# ppc_net.net
KiCad netlist of a schematic drawn in Altium Designer
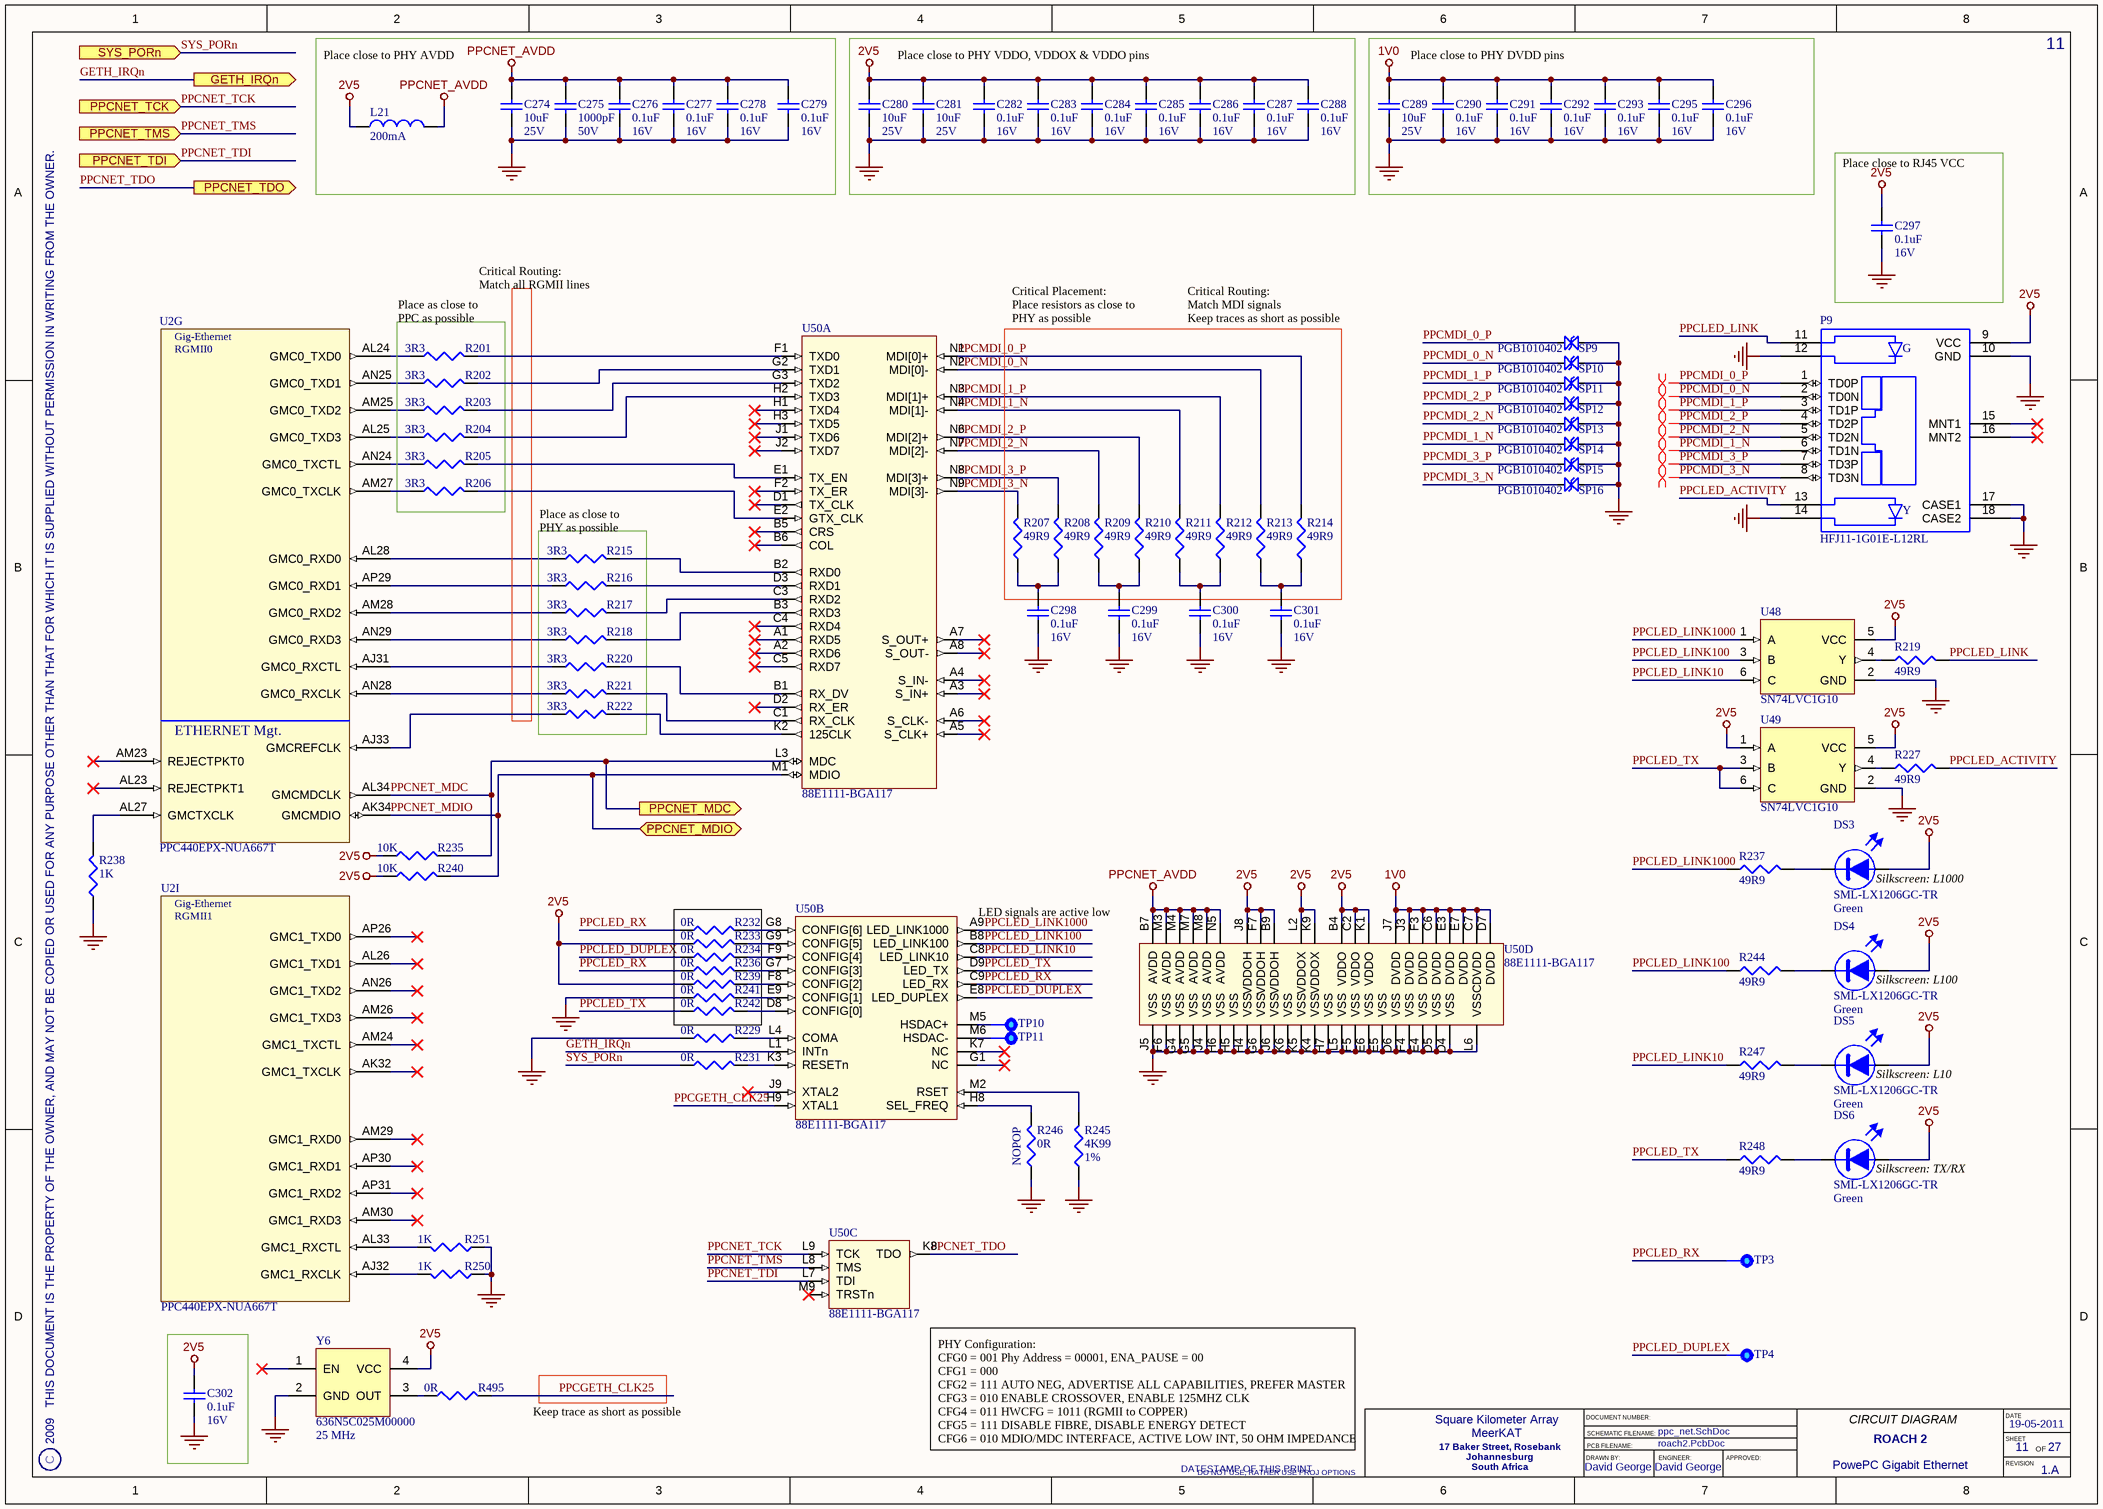
[diagram p0: ppc_net.SchDoc]

(export (version "E")
  (design (tool "Eeschema 10.0.6"))
  (components
    (comp (ref "C274")
      (value "10uF")
      (footprint "CAPC3225X200L")
      (description "10uF, Ceramic Capacitor")
      (fields
        (field (name "RATING") "25V")
        (field (name "MANUFACTURER") "MURATA")
        (field (name "PARTNUM") "GRM32DR61E106KA12L")
      )
      (libsource (lib "altium_db") (part "CapStd"))
    )
    (comp (ref "C275")
      (value "1000pF")
      (footprint "CAPC1005X55L")
      (description "1000pF, Ceramic Capacitor")
      (fields
        (field (name "RATING") "50V")
        (field (name "MANUFACTURER") "MURATA")
        (field (name "PARTNUM") "GRM155R61H102KA01D")
      )
      (libsource (lib "altium_db") (part "CapStd"))
    )
    (comp (ref "C276")
      (value "0.1uF")
      (footprint "CAPC1005X60L")
      (description "0.1uF, Ceramic Capacitor")
      (fields
        (field (name "RATING") "16V")
        (field (name "MANUFACTURER") "VENKEL")
        (field (name "PARTNUM") "C0402X7R160-104KN")
      )
      (libsource (lib "altium_db") (part "CapStd"))
    )
    (comp (ref "C277")
      (value "0.1uF")
      (footprint "CAPC1005X60L")
      (description "0.1uF, Ceramic Capacitor")
      (fields
        (field (name "RATING") "16V")
        (field (name "MANUFACTURER") "VENKEL")
        (field (name "PARTNUM") "C0402X7R160-104KN")
      )
      (libsource (lib "altium_db") (part "CapStd"))
    )
    (comp (ref "C278")
      (value "0.1uF")
      (footprint "CAPC1005X60L")
      (description "0.1uF, Ceramic Capacitor")
      (fields
        (field (name "RATING") "16V")
        (field (name "MANUFACTURER") "VENKEL")
        (field (name "PARTNUM") "C0402X7R160-104KN")
      )
      (libsource (lib "altium_db") (part "CapStd"))
    )
    (comp (ref "C279")
      (value "0.1uF")
      (footprint "CAPC1005X60L")
      (description "0.1uF, Ceramic Capacitor")
      (fields
        (field (name "RATING") "16V")
        (field (name "MANUFACTURER") "VENKEL")
        (field (name "PARTNUM") "C0402X7R160-104KN")
      )
      (libsource (lib "altium_db") (part "CapStd"))
    )
    (comp (ref "C280")
      (value "10uF")
      (footprint "CAPC3225X200L")
      (description "10uF, Ceramic Capacitor")
      (fields
        (field (name "RATING") "25V")
        (field (name "MANUFACTURER") "MURATA")
        (field (name "PARTNUM") "GRM32DR61E106KA12L")
      )
      (libsource (lib "altium_db") (part "CapStd"))
    )
    (comp (ref "C281")
      (value "10uF")
      (footprint "CAPC3225X200L")
      (description "10uF, Ceramic Capacitor")
      (fields
        (field (name "RATING") "25V")
        (field (name "MANUFACTURER") "MURATA")
        (field (name "PARTNUM") "GRM32DR61E106KA12L")
      )
      (libsource (lib "altium_db") (part "CapStd"))
    )
    (comp (ref "C282")
      (value "0.1uF")
      (footprint "CAPC1005X60L")
      (description "0.1uF, Ceramic Capacitor")
      (fields
        (field (name "RATING") "16V")
        (field (name "MANUFACTURER") "VENKEL")
        (field (name "PARTNUM") "C0402X7R160-104KN")
      )
      (libsource (lib "altium_db") (part "CapStd"))
    )
    (comp (ref "C283")
      (value "0.1uF")
      (footprint "CAPC1005X60L")
      (description "0.1uF, Ceramic Capacitor")
      (fields
        (field (name "RATING") "16V")
        (field (name "MANUFACTURER") "VENKEL")
        (field (name "PARTNUM") "C0402X7R160-104KN")
      )
      (libsource (lib "altium_db") (part "CapStd"))
    )
    (comp (ref "C284")
      (value "0.1uF")
      (footprint "CAPC1005X60L")
      (description "0.1uF, Ceramic Capacitor")
      (fields
        (field (name "RATING") "16V")
        (field (name "MANUFACTURER") "VENKEL")
        (field (name "PARTNUM") "C0402X7R160-104KN")
      )
      (libsource (lib "altium_db") (part "CapStd"))
    )
    (comp (ref "C285")
      (value "0.1uF")
      (footprint "CAPC1005X60L")
      (description "0.1uF, Ceramic Capacitor")
      (fields
        (field (name "RATING") "16V")
        (field (name "MANUFACTURER") "VENKEL")
        (field (name "PARTNUM") "C0402X7R160-104KN")
      )
      (libsource (lib "altium_db") (part "CapStd"))
    )
    (comp (ref "C286")
      (value "0.1uF")
      (footprint "CAPC1005X60L")
      (description "0.1uF, Ceramic Capacitor")
      (fields
        (field (name "RATING") "16V")
        (field (name "MANUFACTURER") "VENKEL")
        (field (name "PARTNUM") "C0402X7R160-104KN")
      )
      (libsource (lib "altium_db") (part "CapStd"))
    )
    (comp (ref "C287")
      (value "0.1uF")
      (footprint "CAPC1005X60L")
      (description "0.1uF, Ceramic Capacitor")
      (fields
        (field (name "RATING") "16V")
        (field (name "MANUFACTURER") "VENKEL")
        (field (name "PARTNUM") "C0402X7R160-104KN")
      )
      (libsource (lib "altium_db") (part "CapStd"))
    )
    (comp (ref "C288")
      (value "0.1uF")
      (footprint "CAPC1005X60L")
      (description "0.1uF, Ceramic Capacitor")
      (fields
        (field (name "RATING") "16V")
        (field (name "MANUFACTURER") "VENKEL")
        (field (name "PARTNUM") "C0402X7R160-104KN")
      )
      (libsource (lib "altium_db") (part "CapStd"))
    )
    (comp (ref "C289")
      (value "10uF")
      (footprint "CAPC3225X200L")
      (description "10uF, Ceramic Capacitor")
      (fields
        (field (name "RATING") "25V")
        (field (name "MANUFACTURER") "MURATA")
        (field (name "PARTNUM") "GRM32DR61E106KA12L")
      )
      (libsource (lib "altium_db") (part "CapStd"))
    )
    (comp (ref "C290")
      (value "0.1uF")
      (footprint "CAPC1005X60L")
      (description "0.1uF, Ceramic Capacitor")
      (fields
        (field (name "RATING") "16V")
        (field (name "MANUFACTURER") "VENKEL")
        (field (name "PARTNUM") "C0402X7R160-104KN")
      )
      (libsource (lib "altium_db") (part "CapStd"))
    )
    (comp (ref "C291")
      (value "0.1uF")
      (footprint "CAPC1005X60L")
      (description "0.1uF, Ceramic Capacitor")
      (fields
        (field (name "RATING") "16V")
        (field (name "MANUFACTURER") "VENKEL")
        (field (name "PARTNUM") "C0402X7R160-104KN")
      )
      (libsource (lib "altium_db") (part "CapStd"))
    )
    (comp (ref "C292")
      (value "0.1uF")
      (footprint "CAPC1005X60L")
      (description "0.1uF, Ceramic Capacitor")
      (fields
        (field (name "RATING") "16V")
        (field (name "MANUFACTURER") "VENKEL")
        (field (name "PARTNUM") "C0402X7R160-104KN")
      )
      (libsource (lib "altium_db") (part "CapStd"))
    )
    (comp (ref "C293")
      (value "0.1uF")
      (footprint "CAPC1005X60L")
      (description "0.1uF, Ceramic Capacitor")
      (fields
        (field (name "RATING") "16V")
        (field (name "MANUFACTURER") "VENKEL")
        (field (name "PARTNUM") "C0402X7R160-104KN")
      )
      (libsource (lib "altium_db") (part "CapStd"))
    )
    (comp (ref "C295")
      (value "0.1uF")
      (footprint "CAPC1005X60L")
      (description "0.1uF, Ceramic Capacitor")
      (fields
        (field (name "RATING") "16V")
        (field (name "MANUFACTURER") "VENKEL")
        (field (name "PARTNUM") "C0402X7R160-104KN")
      )
      (libsource (lib "altium_db") (part "CapStd"))
    )
    (comp (ref "C296")
      (value "0.1uF")
      (footprint "CAPC1005X60L")
      (description "0.1uF, Ceramic Capacitor")
      (fields
        (field (name "RATING") "16V")
        (field (name "MANUFACTURER") "VENKEL")
        (field (name "PARTNUM") "C0402X7R160-104KN")
      )
      (libsource (lib "altium_db") (part "CapStd"))
    )
    (comp (ref "C297")
      (value "0.1uF")
      (footprint "CAPC1005X60L")
      (description "0.1uF, Ceramic Capacitor")
      (fields
        (field (name "RATING") "16V")
        (field (name "MANUFACTURER") "VENKEL")
        (field (name "PARTNUM") "C0402X7R160-104KN")
      )
      (libsource (lib "altium_db") (part "CapStd"))
    )
    (comp (ref "C298")
      (value "0.1uF")
      (footprint "CAPC1005X60L")
      (description "0.1uF, Ceramic Capacitor")
      (fields
        (field (name "RATING") "16V")
        (field (name "MANUFACTURER") "VENKEL")
        (field (name "PARTNUM") "C0402X7R160-104KN")
      )
      (libsource (lib "altium_db") (part "CapStd"))
    )
    (comp (ref "C299")
      (value "0.1uF")
      (footprint "CAPC1005X60L")
      (description "0.1uF, Ceramic Capacitor")
      (fields
        (field (name "RATING") "16V")
        (field (name "MANUFACTURER") "VENKEL")
        (field (name "PARTNUM") "C0402X7R160-104KN")
      )
      (libsource (lib "altium_db") (part "CapStd"))
    )
    (comp (ref "C300")
      (value "0.1uF")
      (footprint "CAPC1005X60L")
      (description "0.1uF, Ceramic Capacitor")
      (fields
        (field (name "RATING") "16V")
        (field (name "MANUFACTURER") "VENKEL")
        (field (name "PARTNUM") "C0402X7R160-104KN")
      )
      (libsource (lib "altium_db") (part "CapStd"))
    )
    (comp (ref "C301")
      (value "0.1uF")
      (footprint "CAPC1005X60L")
      (description "0.1uF, Ceramic Capacitor")
      (fields
        (field (name "RATING") "16V")
        (field (name "MANUFACTURER") "VENKEL")
        (field (name "PARTNUM") "C0402X7R160-104KN")
      )
      (libsource (lib "altium_db") (part "CapStd"))
    )
    (comp (ref "C302")
      (value "0.1uF")
      (footprint "CAPC1005X60L")
      (description "0.1uF, Ceramic Capacitor")
      (fields
        (field (name "RATING") "16V")
        (field (name "MANUFACTURER") "VENKEL")
        (field (name "PARTNUM") "C0402X7R160-104KN")
      )
      (libsource (lib "altium_db") (part "CapStd"))
    )
    (comp (ref "DS3")
      (value "SML-LX1206GC-TR")
      (footprint "LEDC3216X120N")
      (description "Green, Surface mount, LED, 1206")
      (fields (field (name "MANUFACTURER") "LUMEX") (field (name "COLOUR") "Green"))
      (libsource (lib "altium_db") (part "LEDSTD"))
    )
    (comp (ref "DS4")
      (value "SML-LX1206GC-TR")
      (footprint "LEDC3216X120N")
      (description "Green, Surface mount, LED, 1206")
      (fields (field (name "MANUFACTURER") "LUMEX") (field (name "COLOUR") "Green"))
      (libsource (lib "altium_db") (part "LEDSTD"))
    )
    (comp (ref "DS5")
      (value "SML-LX1206GC-TR")
      (footprint "LEDC3216X120N")
      (description "Green, Surface mount, LED, 1206")
      (fields (field (name "MANUFACTURER") "LUMEX") (field (name "COLOUR") "Green"))
      (libsource (lib "altium_db") (part "LEDSTD"))
    )
    (comp (ref "DS6")
      (value "SML-LX1206GC-TR")
      (footprint "LEDC3216X120N")
      (description "Green, Surface mount, LED, 1206")
      (fields (field (name "MANUFACTURER") "LUMEX") (field (name "COLOUR") "Green"))
      (libsource (lib "altium_db") (part "LEDSTD"))
    )
    (comp (ref "L21")
      (value "600R")
      (footprint "INDC2012X130L")
      (description "600 Ohm, Chip Ferrite Bead")
      (fields
        (field (name "RATING") "200mA")
        (field (name "MANUFACTURER") "Murata")
        (field (name "PARTNUM") "BLM21BD601SN1")
      )
      (libsource (lib "altium_db") (part "IndStd"))
    )
    (comp (ref "P9")
      (value "HFJ11-1G01E-L12RL")
      (footprint "HALO_HFJ11-1G02E-L55")
      (description "RJ45 with Integrated magnetic and dual LEDs")
      (fields (field (name "PARTNUM") "HFJ11-1G01E-L12RL") (field (name "MANUFACTURER") "HALO"))
      (libsource (lib "altium_db") (part "HFJ11-1G02E-L55"))
    )
    (comp (ref "R201")
      (value "3R3")
      (footprint "RESC1005X40L")
      (description "3R3, 1.1mm x 0.5mm, Thick Film Resistor")
      (fields (field (name "MANUFACTURER") "ROYALOHM") (field (name "PARTNUM") "0402WGJ330KT1E"))
      (libsource (lib "altium_db") (part "ResStd"))
    )
    (comp (ref "R202")
      (value "3R3")
      (footprint "RESC1005X40L")
      (description "3R3, 1.1mm x 0.5mm, Thick Film Resistor")
      (fields (field (name "MANUFACTURER") "ROYALOHM") (field (name "PARTNUM") "0402WGJ330KT1E"))
      (libsource (lib "altium_db") (part "ResStd"))
    )
    (comp (ref "R203")
      (value "3R3")
      (footprint "RESC1005X40L")
      (description "3R3, 1.1mm x 0.5mm, Thick Film Resistor")
      (fields (field (name "MANUFACTURER") "ROYALOHM") (field (name "PARTNUM") "0402WGJ330KT1E"))
      (libsource (lib "altium_db") (part "ResStd"))
    )
    (comp (ref "R204")
      (value "3R3")
      (footprint "RESC1005X40L")
      (description "3R3, 1.1mm x 0.5mm, Thick Film Resistor")
      (fields (field (name "MANUFACTURER") "ROYALOHM") (field (name "PARTNUM") "0402WGJ330KT1E"))
      (libsource (lib "altium_db") (part "ResStd"))
    )
    (comp (ref "R205")
      (value "3R3")
      (footprint "RESC1005X40L")
      (description "3R3, 1.1mm x 0.5mm, Thick Film Resistor")
      (fields (field (name "MANUFACTURER") "ROYALOHM") (field (name "PARTNUM") "0402WGJ330KT1E"))
      (libsource (lib "altium_db") (part "ResStd"))
    )
    (comp (ref "R206")
      (value "3R3")
      (footprint "RESC1005X40L")
      (description "3R3, 1.1mm x 0.5mm, Thick Film Resistor")
      (fields (field (name "MANUFACTURER") "ROYALOHM") (field (name "PARTNUM") "0402WGJ330KT1E"))
      (libsource (lib "altium_db") (part "ResStd"))
    )
    (comp (ref "R207")
      (value "49R9")
      (footprint "RESC1005X40L")
      (description "49R9, 1.1mm x 0.5mm, Thick Film Resistor")
      (fields (field (name "MANUFACTURER") "ROYALOHM") (field (name "PARTNUM") "0402WGF499JT1E"))
      (libsource (lib "altium_db") (part "ResStd"))
    )
    (comp (ref "R208")
      (value "49R9")
      (footprint "RESC1005X40L")
      (description "49R9, 1.1mm x 0.5mm, Thick Film Resistor")
      (fields (field (name "MANUFACTURER") "ROYALOHM") (field (name "PARTNUM") "0402WGF499JT1E"))
      (libsource (lib "altium_db") (part "ResStd"))
    )
    (comp (ref "R209")
      (value "49R9")
      (footprint "RESC1005X40L")
      (description "49R9, 1.1mm x 0.5mm, Thick Film Resistor")
      (fields (field (name "MANUFACTURER") "ROYALOHM") (field (name "PARTNUM") "0402WGF499JT1E"))
      (libsource (lib "altium_db") (part "ResStd"))
    )
    (comp (ref "R210")
      (value "49R9")
      (footprint "RESC1005X40L")
      (description "49R9, 1.1mm x 0.5mm, Thick Film Resistor")
      (fields (field (name "MANUFACTURER") "ROYALOHM") (field (name "PARTNUM") "0402WGF499JT1E"))
      (libsource (lib "altium_db") (part "ResStd"))
    )
    (comp (ref "R211")
      (value "49R9")
      (footprint "RESC1005X40L")
      (description "49R9, 1.1mm x 0.5mm, Thick Film Resistor")
      (fields (field (name "MANUFACTURER") "ROYALOHM") (field (name "PARTNUM") "0402WGF499JT1E"))
      (libsource (lib "altium_db") (part "ResStd"))
    )
    (comp (ref "R212")
      (value "49R9")
      (footprint "RESC1005X40L")
      (description "49R9, 1.1mm x 0.5mm, Thick Film Resistor")
      (fields (field (name "MANUFACTURER") "ROYALOHM") (field (name "PARTNUM") "0402WGF499JT1E"))
      (libsource (lib "altium_db") (part "ResStd"))
    )
    (comp (ref "R213")
      (value "49R9")
      (footprint "RESC1005X40L")
      (description "49R9, 1.1mm x 0.5mm, Thick Film Resistor")
      (fields (field (name "MANUFACTURER") "ROYALOHM") (field (name "PARTNUM") "0402WGF499JT1E"))
      (libsource (lib "altium_db") (part "ResStd"))
    )
    (comp (ref "R214")
      (value "49R9")
      (footprint "RESC1005X40L")
      (description "49R9, 1.1mm x 0.5mm, Thick Film Resistor")
      (fields (field (name "MANUFACTURER") "ROYALOHM") (field (name "PARTNUM") "0402WGF499JT1E"))
      (libsource (lib "altium_db") (part "ResStd"))
    )
    (comp (ref "R215")
      (value "3R3")
      (footprint "RESC1005X40L")
      (description "3R3, 1.1mm x 0.5mm, Thick Film Resistor")
      (fields (field (name "MANUFACTURER") "ROYALOHM") (field (name "PARTNUM") "0402WGJ330KT1E"))
      (libsource (lib "altium_db") (part "ResStd"))
    )
    (comp (ref "R216")
      (value "3R3")
      (footprint "RESC1005X40L")
      (description "3R3, 1.1mm x 0.5mm, Thick Film Resistor")
      (fields (field (name "MANUFACTURER") "ROYALOHM") (field (name "PARTNUM") "0402WGJ330KT1E"))
      (libsource (lib "altium_db") (part "ResStd"))
    )
    (comp (ref "R217")
      (value "3R3")
      (footprint "RESC1005X40L")
      (description "3R3, 1.1mm x 0.5mm, Thick Film Resistor")
      (fields (field (name "MANUFACTURER") "ROYALOHM") (field (name "PARTNUM") "0402WGJ330KT1E"))
      (libsource (lib "altium_db") (part "ResStd"))
    )
    (comp (ref "R218")
      (value "3R3")
      (footprint "RESC1005X40L")
      (description "3R3, 1.1mm x 0.5mm, Thick Film Resistor")
      (fields (field (name "MANUFACTURER") "ROYALOHM") (field (name "PARTNUM") "0402WGJ330KT1E"))
      (libsource (lib "altium_db") (part "ResStd"))
    )
    (comp (ref "R219")
      (value "49R9")
      (footprint "RESC1005X40L")
      (description "49R9, 1.1mm x 0.5mm, Thick Film Resistor")
      (fields (field (name "MANUFACTURER") "ROYALOHM") (field (name "PARTNUM") "0402WGF499JT1E"))
      (libsource (lib "altium_db") (part "ResStd"))
    )
    (comp (ref "R220")
      (value "3R3")
      (footprint "RESC1005X40L")
      (description "3R3, 1.1mm x 0.5mm, Thick Film Resistor")
      (fields (field (name "MANUFACTURER") "ROYALOHM") (field (name "PARTNUM") "0402WGJ330KT1E"))
      (libsource (lib "altium_db") (part "ResStd"))
    )
    (comp (ref "R221")
      (value "3R3")
      (footprint "RESC1005X40L")
      (description "3R3, 1.1mm x 0.5mm, Thick Film Resistor")
      (fields (field (name "MANUFACTURER") "ROYALOHM") (field (name "PARTNUM") "0402WGJ330KT1E"))
      (libsource (lib "altium_db") (part "ResStd"))
    )
    (comp (ref "R222")
      (value "3R3")
      (footprint "RESC1005X40L")
      (description "3R3, 1.1mm x 0.5mm, Thick Film Resistor")
      (fields (field (name "MANUFACTURER") "ROYALOHM") (field (name "PARTNUM") "0402WGJ330KT1E"))
      (libsource (lib "altium_db") (part "ResStd"))
    )
    (comp (ref "R227")
      (value "49R9")
      (footprint "RESC1005X40L")
      (description "49R9, 1.1mm x 0.5mm, Thick Film Resistor")
      (fields (field (name "MANUFACTURER") "ROYALOHM") (field (name "PARTNUM") "0402WGF499JT1E"))
      (libsource (lib "altium_db") (part "ResStd"))
    )
    (comp (ref "R229")
      (value "0R")
      (footprint "RESC1005X40L")
      (description "0R, 1.1mm x 0.5mm, Thick Film Resistor")
      (fields (field (name "MANUFACTURER") "ROYALOHM") (field (name "PARTNUM") "0402WG00000T1E"))
      (libsource (lib "altium_db") (part "ResStd"))
    )
    (comp (ref "R231")
      (value "0R")
      (footprint "RESC1005X40L")
      (description "0R, 1.1mm x 0.5mm, Thick Film Resistor")
      (fields (field (name "MANUFACTURER") "ROYALOHM") (field (name "PARTNUM") "0402WG00000T1E"))
      (libsource (lib "altium_db") (part "ResStd"))
    )
    (comp (ref "R232")
      (value "0R")
      (footprint "RESC1005X40L")
      (description "0R, 1.1mm x 0.5mm, Thick Film Resistor")
      (fields (field (name "MANUFACTURER") "ROYALOHM") (field (name "PARTNUM") "0402WG00000T1E"))
      (libsource (lib "altium_db") (part "ResStd"))
    )
    (comp (ref "R233")
      (value "0R")
      (footprint "RESC1005X40L")
      (description "0R, 1.1mm x 0.5mm, Thick Film Resistor")
      (fields (field (name "MANUFACTURER") "ROYALOHM") (field (name "PARTNUM") "0402WG00000T1E"))
      (libsource (lib "altium_db") (part "ResStd"))
    )
    (comp (ref "R234")
      (value "0R")
      (footprint "RESC1005X40L")
      (description "0R, 1.1mm x 0.5mm, Thick Film Resistor")
      (fields (field (name "MANUFACTURER") "ROYALOHM") (field (name "PARTNUM") "0402WG00000T1E"))
      (libsource (lib "altium_db") (part "ResStd"))
    )
    (comp (ref "R235")
      (value "10K")
      (footprint "RESC1005X40L")
      (description "10K, 1.1mm x 0.5mm, Thick Film Resistor")
      (fields (field (name "MANUFACTURER") "ROYALOHM") (field (name "PARTNUM") "0402WGJ0103T1E"))
      (libsource (lib "altium_db") (part "ResStd"))
    )
    (comp (ref "R236")
      (value "0R")
      (footprint "RESC1005X40L")
      (description "0R, 1.1mm x 0.5mm, Thick Film Resistor")
      (fields (field (name "MANUFACTURER") "ROYALOHM") (field (name "PARTNUM") "0402WG00000T1E"))
      (libsource (lib "altium_db") (part "ResStd"))
    )
    (comp (ref "R237")
      (value "49R9")
      (footprint "RESC1005X40L")
      (description "49R9, 1.1mm x 0.5mm, Thick Film Resistor")
      (fields (field (name "MANUFACTURER") "ROYALOHM") (field (name "PARTNUM") "0402WGF499JT1E"))
      (libsource (lib "altium_db") (part "ResStd"))
    )
    (comp (ref "R238")
      (value "1K")
      (footprint "RESC1005X40L")
      (description "1K, 1.1mm x 0.5mm, Thick Film Resistor")
      (fields (field (name "MANUFACTURER") "ROYALOHM") (field (name "PARTNUM") "0402WGJ0102T1E"))
      (libsource (lib "altium_db") (part "ResStd"))
    )
    (comp (ref "R239")
      (value "0R")
      (footprint "RESC1005X40L")
      (description "0R, 1.1mm x 0.5mm, Thick Film Resistor")
      (fields (field (name "MANUFACTURER") "ROYALOHM") (field (name "PARTNUM") "0402WG00000T1E"))
      (libsource (lib "altium_db") (part "ResStd"))
    )
    (comp (ref "R240")
      (value "10K")
      (footprint "RESC1005X40L")
      (description "10K, 1.1mm x 0.5mm, Thick Film Resistor")
      (fields (field (name "MANUFACTURER") "ROYALOHM") (field (name "PARTNUM") "0402WGJ0103T1E"))
      (libsource (lib "altium_db") (part "ResStd"))
    )
    (comp (ref "R241")
      (value "0R")
      (footprint "RESC1005X40L")
      (description "0R, 1.1mm x 0.5mm, Thick Film Resistor")
      (fields (field (name "MANUFACTURER") "ROYALOHM") (field (name "PARTNUM") "0402WG00000T1E"))
      (libsource (lib "altium_db") (part "ResStd"))
    )
    (comp (ref "R242")
      (value "0R")
      (footprint "RESC1005X40L")
      (description "0R, 1.1mm x 0.5mm, Thick Film Resistor")
      (fields (field (name "MANUFACTURER") "ROYALOHM") (field (name "PARTNUM") "0402WG00000T1E"))
      (libsource (lib "altium_db") (part "ResStd"))
    )
    (comp (ref "R244")
      (value "49R9")
      (footprint "RESC1005X40L")
      (description "49R9, 1.1mm x 0.5mm, Thick Film Resistor")
      (fields (field (name "MANUFACTURER") "ROYALOHM") (field (name "PARTNUM") "0402WGF499JT1E"))
      (libsource (lib "altium_db") (part "ResStd"))
    )
    (comp (ref "R245")
      (value "4K99")
      (footprint "RESC1005X40L")
      (description "4K99, 1.1mm x 0.5mm, Thick Film Resistor")
      (fields
        (field (name "MANUFACTURER") "ROYALOHM")
        (field (name "PARTNUM") "0402WGF4991T1E")
        (field (name "TOLERANCE") "1%")
      )
      (libsource (lib "altium_db") (part "ResStd"))
    )
    (comp (ref "R246")
      (value "0R")
      (footprint "RESC1005X40L")
      (description "0R, 1.1mm x 0.5mm, Thick Film Resistor")
      (fields (field (name "MANUFACTURER") "ROYALOHM") (field (name "PARTNUM") "0402WG00000T1E"))
      (libsource (lib "altium_db") (part "ResStd"))
    )
    (comp (ref "R247")
      (value "49R9")
      (footprint "RESC1005X40L")
      (description "49R9, 1.1mm x 0.5mm, Thick Film Resistor")
      (fields (field (name "MANUFACTURER") "ROYALOHM") (field (name "PARTNUM") "0402WGF499JT1E"))
      (libsource (lib "altium_db") (part "ResStd"))
    )
    (comp (ref "R248")
      (value "49R9")
      (footprint "RESC1005X40L")
      (description "49R9, 1.1mm x 0.5mm, Thick Film Resistor")
      (fields (field (name "MANUFACTURER") "ROYALOHM") (field (name "PARTNUM") "0402WGF499JT1E"))
      (libsource (lib "altium_db") (part "ResStd"))
    )
    (comp (ref "R250")
      (value "1K")
      (footprint "RESC1005X40L")
      (description "1K, 1.1mm x 0.5mm, Thick Film Resistor")
      (fields (field (name "MANUFACTURER") "ROYALOHM") (field (name "PARTNUM") "0402WGJ0102T1E"))
      (libsource (lib "altium_db") (part "ResStd"))
    )
    (comp (ref "R251")
      (value "1K")
      (footprint "RESC1005X40L")
      (description "1K, 1.1mm x 0.5mm, Thick Film Resistor")
      (fields (field (name "MANUFACTURER") "ROYALOHM") (field (name "PARTNUM") "0402WGJ0102T1E"))
      (libsource (lib "altium_db") (part "ResStd"))
    )
    (comp (ref "R495")
      (value "0R")
      (footprint "RESC1005X40L")
      (description "0R, 1.1mm x 0.5mm, Thick Film Resistor")
      (fields (field (name "MANUFACTURER") "ROYALOHM") (field (name "PARTNUM") "0402WG00000T1E"))
      (libsource (lib "altium_db") (part "ResStd"))
    )
    (comp (ref "SP9")
      (value "PGB1010402")
      (footprint "PGB1010402")
      (description "Surface Mount Polymeric ESD Suppressor in an 0402 package")
      (fields (field (name "PARTNUM") "PGB1010402"))
      (libsource (lib "altium_db") (part "PGB1010402"))
    )
    (comp (ref "SP10")
      (value "PGB1010402")
      (footprint "PGB1010402")
      (description "Surface Mount Polymeric ESD Suppressor in an 0402 package")
      (fields (field (name "PARTNUM") "PGB1010402"))
      (libsource (lib "altium_db") (part "PGB1010402"))
    )
    (comp (ref "SP11")
      (value "PGB1010402")
      (footprint "PGB1010402")
      (description "Surface Mount Polymeric ESD Suppressor in an 0402 package")
      (fields (field (name "PARTNUM") "PGB1010402"))
      (libsource (lib "altium_db") (part "PGB1010402"))
    )
    (comp (ref "SP12")
      (value "PGB1010402")
      (footprint "PGB1010402")
      (description "Surface Mount Polymeric ESD Suppressor in an 0402 package")
      (fields (field (name "PARTNUM") "PGB1010402"))
      (libsource (lib "altium_db") (part "PGB1010402"))
    )
    (comp (ref "SP13")
      (value "PGB1010402")
      (footprint "PGB1010402")
      (description "Surface Mount Polymeric ESD Suppressor in an 0402 package")
      (fields (field (name "PARTNUM") "PGB1010402"))
      (libsource (lib "altium_db") (part "PGB1010402"))
    )
    (comp (ref "SP14")
      (value "PGB1010402")
      (footprint "PGB1010402")
      (description "Surface Mount Polymeric ESD Suppressor in an 0402 package")
      (fields (field (name "PARTNUM") "PGB1010402"))
      (libsource (lib "altium_db") (part "PGB1010402"))
    )
    (comp (ref "SP15")
      (value "PGB1010402")
      (footprint "PGB1010402")
      (description "Surface Mount Polymeric ESD Suppressor in an 0402 package")
      (fields (field (name "PARTNUM") "PGB1010402"))
      (libsource (lib "altium_db") (part "PGB1010402"))
    )
    (comp (ref "SP16")
      (value "PGB1010402")
      (footprint "PGB1010402")
      (description "Surface Mount Polymeric ESD Suppressor in an 0402 package")
      (fields (field (name "PARTNUM") "PGB1010402"))
      (libsource (lib "altium_db") (part "PGB1010402"))
    )
    (comp (ref "TP3")
      (value "Testpoint")
      (footprint "TP100")
      (description "1mm Diameter, through-hole, Circular Test-point")
      (libsource (lib "altium_db") (part "Testpoint"))
    )
    (comp (ref "TP4")
      (value "Testpoint")
      (footprint "TP100")
      (description "1mm Diameter, through-hole, Circular Test-point")
      (libsource (lib "altium_db") (part "Testpoint"))
    )
    (comp (ref "TP10")
      (value "Testpoint")
      (footprint "TP100")
      (description "1mm Diameter, through-hole, Circular Test-point")
      (libsource (lib "altium_db") (part "Testpoint"))
    )
    (comp (ref "TP11")
      (value "Testpoint")
      (footprint "TP100")
      (description "1mm Diameter, through-hole, Circular Test-point")
      (libsource (lib "altium_db") (part "Testpoint"))
    )
    (comp (ref "U2")
      (value "PPC440EPX-NUA667T")
      (footprint "TE-PBGA680")
      (description "667MHz, non-RoHS, PPC440EPx uProcessor")
      (fields (field (name "MANUFACTURER") "Applied Micro"))
      (libsource (lib "altium_db") (part "PPC440EPX"))
    )
    (comp (ref "U48")
      (value "SN74LVC1G10")
      (footprint "SOT23-6")
      (description "Single 3-input Positive-NAND gate")
      (fields (field (name "MANUFACTURER") "Texas Instruments"))
      (libsource (lib "altium_db") (part "SN74LVC1G10"))
    )
    (comp (ref "U49")
      (value "SN74LVC1G10")
      (footprint "SOT23-6")
      (description "Single 3-input Positive-NAND gate")
      (fields (field (name "MANUFACTURER") "Texas Instruments"))
      (libsource (lib "altium_db") (part "SN74LVC1G10"))
    )
    (comp (ref "U50")
      (value "88E1111-BGA117")
      (footprint "BGA117C100P13X9_1400X1000X154")
      (description "Integrated 10/100/1000 Ultra Gigabit Ethernet Transceiver")
      (fields (field (name "MANUFACTURER") "Marvell") (field (name "PARTNUM") "88E1111-XX-BAB1C000"))
      (libsource (lib "altium_db") (part "88E1111-TFBGA117"))
    )
    (comp (ref "Y6")
      (value "636N5C025M00000")
      (footprint "636XXXXXXMXXXXX")
      (description "25.00 MHz, 2V5, CTS 636 clock oscillator")
      (fields
        (field (name "PARTNUM") "636N5C025M00000")
        (field (name "FREQUENCY") "25 MHz")
        (field (name "MANUFACTURER") "CTS")
      )
      (libsource (lib "altium_db") (part "636XXXXXXMXXXXX"))
    )
  )
  (nets
    (net (code "1") (name "/GETH_IRQn") (class "Default")
      (node (ref "U50") (pin "L1") (pinfunction "INTn_L1") (pintype "input"))
    )
    (net (code "2") (name "/PPCGETH_CLK25") (class "Default")
      (node (ref "R495") (pin "2") (pinfunction "2_2") (pintype "passive"))
      (node (ref "U50") (pin "H9") (pinfunction "XTAL1_H9") (pintype "input"))
    )
    (net (code "3") (name "/PPCLED_ACTIVITY") (class "Default")
      (node (ref "P9") (pin "13") (pinfunction "L1_YC_GA_13") (pintype "passive"))
      (node (ref "R227") (pin "2") (pinfunction "2_2") (pintype "passive"))
    )
    (net (code "4") (name "/PPCLED_DUPLEX") (class "Default")
      (node (ref "R234") (pin "1") (pinfunction "1_1") (pintype "passive"))
      (node (ref "TP4") (pin "1") (pinfunction "1_1") (pintype "passive"))
      (node (ref "U50") (pin "E8") (pinfunction "LED_DUPLEX_E8") (pintype "output"))
    )
    (net (code "5") (name "/PPCLED_LINK") (class "Default")
      (node (ref "P9") (pin "11") (pinfunction "R1_YC_GA_11") (pintype "passive"))
      (node (ref "R219") (pin "2") (pinfunction "2_2") (pintype "passive"))
    )
    (net (code "6") (name "/PPCLED_LINK10") (class "Default")
      (node (ref "R247") (pin "1") (pinfunction "1_1") (pintype "passive"))
      (node (ref "U48") (pin "6") (pinfunction "C_6") (pintype "input"))
      (node (ref "U50") (pin "C8") (pinfunction "LED_LINK10_C8") (pintype "output"))
    )
    (net (code "7") (name "/PPCLED_LINK100") (class "Default")
      (node (ref "R244") (pin "1") (pinfunction "1_1") (pintype "passive"))
      (node (ref "U48") (pin "3") (pinfunction "B_3") (pintype "input"))
      (node (ref "U50") (pin "B8") (pinfunction "LED_LINK100_B8") (pintype "output"))
    )
    (net (code "8") (name "/PPCLED_LINK1000") (class "Default")
      (node (ref "R237") (pin "1") (pinfunction "1_1") (pintype "passive"))
      (node (ref "U48") (pin "1") (pinfunction "A_1") (pintype "input"))
      (node (ref "U50") (pin "A9") (pinfunction "LED_LINK1000_A9") (pintype "output"))
    )
    (net (code "9") (name "/PPCLED_RX") (class "Default")
      (node (ref "R232") (pin "1") (pinfunction "1_1") (pintype "passive"))
      (node (ref "R236") (pin "1") (pinfunction "1_1") (pintype "passive"))
      (node (ref "TP3") (pin "1") (pinfunction "1_1") (pintype "passive"))
      (node (ref "U50") (pin "C9") (pinfunction "LED_RX_C9") (pintype "output"))
    )
    (net (code "10") (name "/PPCLED_TX") (class "Default")
      (node (ref "R242") (pin "1") (pinfunction "1_1") (pintype "passive"))
      (node (ref "R248") (pin "1") (pinfunction "1_1") (pintype "passive"))
      (node (ref "U49") (pin "3") (pinfunction "B_3") (pintype "input"))
      (node (ref "U49") (pin "6") (pinfunction "C_6") (pintype "input"))
      (node (ref "U50") (pin "D9") (pinfunction "LED_TX_D9") (pintype "output"))
    )
    (net (code "11") (name "/PPCMDI_0_N") (class "Default")
      (node (ref "P9") (pin "2") (pinfunction "TD0N_2") (pintype "bidirectional"))
      (node (ref "R213") (pin "2") (pinfunction "2_2") (pintype "passive"))
      (node (ref "SP10") (pin "2") (pinfunction "B_2") (pintype "passive"))
      (node (ref "U50") (pin "N2") (pinfunction "MDI[0]-_N2") (pintype "input"))
    )
    (net (code "12") (name "/PPCMDI_0_P") (class "Default")
      (node (ref "P9") (pin "1") (pinfunction "TD0P_1") (pintype "bidirectional"))
      (node (ref "R214") (pin "2") (pinfunction "2_2") (pintype "passive"))
      (node (ref "SP9") (pin "2") (pinfunction "B_2") (pintype "passive"))
      (node (ref "U50") (pin "N1") (pinfunction "MDI[0]+_N1") (pintype "input"))
    )
    (net (code "13") (name "/PPCMDI_1_N") (class "Default")
      (node (ref "P9") (pin "6") (pinfunction "TD1N_6") (pintype "bidirectional"))
      (node (ref "R211") (pin "2") (pinfunction "2_2") (pintype "passive"))
      (node (ref "SP14") (pin "2") (pinfunction "B_2") (pintype "passive"))
      (node (ref "U50") (pin "N4") (pinfunction "MDI[1]-_N4") (pintype "input"))
    )
    (net (code "14") (name "/PPCMDI_1_P") (class "Default")
      (node (ref "P9") (pin "3") (pinfunction "TD1P_3") (pintype "bidirectional"))
      (node (ref "R212") (pin "2") (pinfunction "2_2") (pintype "passive"))
      (node (ref "SP11") (pin "2") (pinfunction "B_2") (pintype "passive"))
      (node (ref "U50") (pin "N3") (pinfunction "MDI[1]+_N3") (pintype "input"))
    )
    (net (code "15") (name "/PPCMDI_2_N") (class "Default")
      (node (ref "P9") (pin "5") (pinfunction "TD2N_5") (pintype "bidirectional"))
      (node (ref "R209") (pin "2") (pinfunction "2_2") (pintype "passive"))
      (node (ref "SP13") (pin "2") (pinfunction "B_2") (pintype "passive"))
      (node (ref "U50") (pin "N7") (pinfunction "MDI[2]-_N7") (pintype "input"))
    )
    (net (code "16") (name "/PPCMDI_2_P") (class "Default")
      (node (ref "P9") (pin "4") (pinfunction "TD2P_4") (pintype "bidirectional"))
      (node (ref "R210") (pin "2") (pinfunction "2_2") (pintype "passive"))
      (node (ref "SP12") (pin "2") (pinfunction "B_2") (pintype "passive"))
      (node (ref "U50") (pin "N6") (pinfunction "MDI[2]+_N6") (pintype "output"))
    )
    (net (code "17") (name "/PPCMDI_3_N") (class "Default")
      (node (ref "P9") (pin "8") (pinfunction "TD3N_8") (pintype "bidirectional"))
      (node (ref "R207") (pin "2") (pinfunction "2_2") (pintype "passive"))
      (node (ref "SP16") (pin "2") (pinfunction "B_2") (pintype "passive"))
      (node (ref "U50") (pin "N9") (pinfunction "MDI[3]-_N9") (pintype "output"))
    )
    (net (code "18") (name "/PPCMDI_3_P") (class "Default")
      (node (ref "P9") (pin "7") (pinfunction "TD3P_7") (pintype "bidirectional"))
      (node (ref "R208") (pin "2") (pinfunction "2_2") (pintype "passive"))
      (node (ref "SP15") (pin "2") (pinfunction "B_2") (pintype "passive"))
      (node (ref "U50") (pin "N8") (pinfunction "MDI[3]+_N8") (pintype "output"))
    )
    (net (code "19") (name "/PPCNET_MDC") (class "Default")
      (node (ref "R235") (pin "2") (pinfunction "2_2") (pintype "passive"))
      (node (ref "U2") (pin "AL34") (pinfunction "GMCMDCLK_AL34") (pintype "output"))
      (node (ref "U50") (pin "L3") (pinfunction "MDC_L3") (pintype "bidirectional"))
    )
    (net (code "20") (name "/PPCNET_MDIO") (class "Default")
      (node (ref "R240") (pin "2") (pinfunction "2_2") (pintype "passive"))
      (node (ref "U2") (pin "AK34") (pinfunction "GMCMDIO_AK34") (pintype "bidirectional"))
      (node (ref "U50") (pin "M1") (pinfunction "MDIO_M1") (pintype "bidirectional"))
    )
    (net (code "21") (name "/PPCNET_TCK") (class "Default")
      (node (ref "U50") (pin "L9") (pinfunction "TCK_L9") (pintype "input"))
    )
    (net (code "22") (name "/PPCNET_TDI") (class "Default")
      (node (ref "U50") (pin "L7") (pinfunction "TDI_L7") (pintype "input"))
    )
    (net (code "23") (name "/PPCNET_TDO") (class "Default")
      (node (ref "U50") (pin "K8") (pinfunction "TDO_K8") (pintype "output"))
    )
    (net (code "24") (name "/PPCNET_TMS") (class "Default")
      (node (ref "U50") (pin "L8") (pinfunction "TMS_L8") (pintype "input"))
    )
    (net (code "25") (name "/SYS_PORn") (class "Default")
      (node (ref "R231") (pin "1") (pinfunction "1_1") (pintype "passive"))
    )
    (net (code "26") (name "1V0") (class "Default")
      (node (ref "C289") (pin "2") (pinfunction "2_2") (pintype "passive"))
      (node (ref "C290") (pin "2") (pinfunction "2_2") (pintype "passive"))
      (node (ref "C291") (pin "2") (pinfunction "2_2") (pintype "passive"))
      (node (ref "C292") (pin "2") (pinfunction "2_2") (pintype "passive"))
      (node (ref "C293") (pin "2") (pinfunction "2_2") (pintype "passive"))
      (node (ref "C295") (pin "2") (pinfunction "2_2") (pintype "passive"))
      (node (ref "C296") (pin "2") (pinfunction "2_2") (pintype "passive"))
      (node (ref "U50") (pin "C6") (pinfunction "DVDD_C6") (pintype "power_in"))
      (node (ref "U50") (pin "C7") (pinfunction "DVDD_C7") (pintype "power_in"))
      (node (ref "U50") (pin "D7") (pinfunction "DVDD_D7") (pintype "power_in"))
      (node (ref "U50") (pin "E3") (pinfunction "DVDD_E3") (pintype "power_in"))
      (node (ref "U50") (pin "E7") (pinfunction "DVDD_E7") (pintype "power_in"))
      (node (ref "U50") (pin "F3") (pinfunction "DVDD_F3") (pintype "power_in"))
      (node (ref "U50") (pin "J3") (pinfunction "DVDD_J3") (pintype "power_in"))
      (node (ref "U50") (pin "J7") (pinfunction "DVDD_J7") (pintype "power_in"))
    )
    (net (code "27") (name "2V5") (class "Default")
      (node (ref "C280") (pin "2") (pinfunction "2_2") (pintype "passive"))
      (node (ref "C281") (pin "2") (pinfunction "2_2") (pintype "passive"))
      (node (ref "C282") (pin "2") (pinfunction "2_2") (pintype "passive"))
      (node (ref "C283") (pin "2") (pinfunction "2_2") (pintype "passive"))
      (node (ref "C284") (pin "2") (pinfunction "2_2") (pintype "passive"))
      (node (ref "C285") (pin "2") (pinfunction "2_2") (pintype "passive"))
      (node (ref "C286") (pin "2") (pinfunction "2_2") (pintype "passive"))
      (node (ref "C287") (pin "2") (pinfunction "2_2") (pintype "passive"))
      (node (ref "C288") (pin "2") (pinfunction "2_2") (pintype "passive"))
      (node (ref "C297") (pin "2") (pinfunction "2_2") (pintype "passive"))
      (node (ref "C302") (pin "2") (pinfunction "2_2") (pintype "passive"))
      (node (ref "DS3") (pin "2") (pinfunction "A_2") (pintype "passive"))
      (node (ref "DS4") (pin "2") (pinfunction "A_2") (pintype "passive"))
      (node (ref "DS5") (pin "2") (pinfunction "A_2") (pintype "passive"))
      (node (ref "DS6") (pin "2") (pinfunction "A_2") (pintype "passive"))
      (node (ref "L21") (pin "1") (pinfunction "1_1") (pintype "passive"))
      (node (ref "P9") (pin "9") (pinfunction "VCC_9") (pintype "power_in"))
      (node (ref "R233") (pin "1") (pinfunction "1_1") (pintype "passive"))
      (node (ref "R235") (pin "1") (pinfunction "1_1") (pintype "passive"))
      (node (ref "R239") (pin "1") (pinfunction "1_1") (pintype "passive"))
      (node (ref "R240") (pin "1") (pinfunction "1_1") (pintype "passive"))
      (node (ref "U48") (pin "5") (pinfunction "VCC_5") (pintype "power_in"))
      (node (ref "U49") (pin "1") (pinfunction "A_1") (pintype "input"))
      (node (ref "U49") (pin "5") (pinfunction "VCC_5") (pintype "power_in"))
      (node (ref "U50") (pin "B4") (pinfunction "VDDO_B4") (pintype "power_in"))
      (node (ref "U50") (pin "B9") (pinfunction "VDDOH_B9") (pintype "power_in"))
      (node (ref "U50") (pin "C2") (pinfunction "VDDO_C2") (pintype "power_in"))
      (node (ref "U50") (pin "F7") (pinfunction "VDDOH_F7") (pintype "power_in"))
      (node (ref "U50") (pin "J8") (pinfunction "VDDOH_J8") (pintype "power_in"))
      (node (ref "U50") (pin "K1") (pinfunction "VDDO_K1") (pintype "power_in"))
      (node (ref "U50") (pin "K9") (pinfunction "VDDOX_K9") (pintype "power_in"))
      (node (ref "U50") (pin "L2") (pinfunction "VDDOX_L2") (pintype "power_in"))
      (node (ref "Y6") (pin "4") (pinfunction "VCC_4") (pintype "passive"))
    )
    (net (code "28") (name "GND") (class "Default")
      (node (ref "C274") (pin "1") (pinfunction "1_1") (pintype "passive"))
      (node (ref "C275") (pin "1") (pinfunction "1_1") (pintype "passive"))
      (node (ref "C276") (pin "1") (pinfunction "1_1") (pintype "passive"))
      (node (ref "C277") (pin "1") (pinfunction "1_1") (pintype "passive"))
      (node (ref "C278") (pin "1") (pinfunction "1_1") (pintype "passive"))
      (node (ref "C279") (pin "1") (pinfunction "1_1") (pintype "passive"))
      (node (ref "C280") (pin "1") (pinfunction "1_1") (pintype "passive"))
      (node (ref "C281") (pin "1") (pinfunction "1_1") (pintype "passive"))
      (node (ref "C282") (pin "1") (pinfunction "1_1") (pintype "passive"))
      (node (ref "C283") (pin "1") (pinfunction "1_1") (pintype "passive"))
      (node (ref "C284") (pin "1") (pinfunction "1_1") (pintype "passive"))
      (node (ref "C285") (pin "1") (pinfunction "1_1") (pintype "passive"))
      (node (ref "C286") (pin "1") (pinfunction "1_1") (pintype "passive"))
      (node (ref "C287") (pin "1") (pinfunction "1_1") (pintype "passive"))
      (node (ref "C288") (pin "1") (pinfunction "1_1") (pintype "passive"))
      (node (ref "C289") (pin "1") (pinfunction "1_1") (pintype "passive"))
      (node (ref "C290") (pin "1") (pinfunction "1_1") (pintype "passive"))
      (node (ref "C291") (pin "1") (pinfunction "1_1") (pintype "passive"))
      (node (ref "C292") (pin "1") (pinfunction "1_1") (pintype "passive"))
      (node (ref "C293") (pin "1") (pinfunction "1_1") (pintype "passive"))
      (node (ref "C295") (pin "1") (pinfunction "1_1") (pintype "passive"))
      (node (ref "C296") (pin "1") (pinfunction "1_1") (pintype "passive"))
      (node (ref "C297") (pin "1") (pinfunction "1_1") (pintype "passive"))
      (node (ref "C298") (pin "2") (pinfunction "2_2") (pintype "passive"))
      (node (ref "C299") (pin "2") (pinfunction "2_2") (pintype "passive"))
      (node (ref "C300") (pin "2") (pinfunction "2_2") (pintype "passive"))
      (node (ref "C301") (pin "2") (pinfunction "2_2") (pintype "passive"))
      (node (ref "C302") (pin "1") (pinfunction "1_1") (pintype "passive"))
      (node (ref "P9") (pin "10") (pinfunction "GND_10") (pintype "power_in"))
      (node (ref "P9") (pin "12") (pinfunction "R1_YA_GC_12") (pintype "passive"))
      (node (ref "P9") (pin "14") (pinfunction "L1_YA_GC_14") (pintype "passive"))
      (node (ref "P9") (pin "17") (pinfunction "CASE1_17") (pintype "power_in"))
      (node (ref "P9") (pin "18") (pinfunction "CASE2_18") (pintype "power_in"))
      (node (ref "R229") (pin "1") (pinfunction "1_1") (pintype "passive"))
      (node (ref "R238") (pin "1") (pinfunction "1_1") (pintype "passive"))
      (node (ref "R241") (pin "1") (pinfunction "1_1") (pintype "passive"))
      (node (ref "R245") (pin "1") (pinfunction "1_1") (pintype "passive"))
      (node (ref "R246") (pin "1") (pinfunction "1_1") (pintype "passive"))
      (node (ref "R250") (pin "1") (pinfunction "1_1") (pintype "passive"))
      (node (ref "R251") (pin "1") (pinfunction "1_1") (pintype "passive"))
      (node (ref "SP10") (pin "1") (pinfunction "A_1") (pintype "passive"))
      (node (ref "SP11") (pin "1") (pinfunction "A_1") (pintype "passive"))
      (node (ref "SP12") (pin "1") (pinfunction "A_1") (pintype "passive"))
      (node (ref "SP13") (pin "1") (pinfunction "A_1") (pintype "passive"))
      (node (ref "SP14") (pin "1") (pinfunction "A_1") (pintype "passive"))
      (node (ref "SP15") (pin "1") (pinfunction "A_1") (pintype "passive"))
      (node (ref "SP16") (pin "1") (pinfunction "A_1") (pintype "passive"))
      (node (ref "SP9") (pin "1") (pinfunction "A_1") (pintype "passive"))
      (node (ref "U48") (pin "2") (pinfunction "GND_2") (pintype "power_in"))
      (node (ref "U49") (pin "2") (pinfunction "GND_2") (pintype "power_in"))
      (node (ref "U50") (pin "D4") (pinfunction "VSS_D4") (pintype "power_in"))
      (node (ref "U50") (pin "D5") (pinfunction "VSS_D5") (pintype "power_in"))
      (node (ref "U50") (pin "D6") (pinfunction "VSS_D6") (pintype "power_in"))
      (node (ref "U50") (pin "E4") (pinfunction "VSS_E4") (pintype "power_in"))
      (node (ref "U50") (pin "E5") (pinfunction "VSS_E5") (pintype "power_in"))
      (node (ref "U50") (pin "E6") (pinfunction "VSS_E6") (pintype "power_in"))
      (node (ref "U50") (pin "F4") (pinfunction "VSS_F4") (pintype "power_in"))
      (node (ref "U50") (pin "F5") (pinfunction "VSS_F5") (pintype "power_in"))
      (node (ref "U50") (pin "F6") (pinfunction "VSS_F6") (pintype "power_in"))
      (node (ref "U50") (pin "G4") (pinfunction "VSS_G4") (pintype "power_in"))
      (node (ref "U50") (pin "G5") (pinfunction "VSS_G5") (pintype "power_in"))
      (node (ref "U50") (pin "G6") (pinfunction "VSS_G6") (pintype "power_in"))
      (node (ref "U50") (pin "H4") (pinfunction "VSS_H4") (pintype "power_in"))
      (node (ref "U50") (pin "H5") (pinfunction "VSS_H5") (pintype "power_in"))
      (node (ref "U50") (pin "H6") (pinfunction "VSS_H6") (pintype "power_in"))
      (node (ref "U50") (pin "H7") (pinfunction "VSS_H7") (pintype "power_in"))
      (node (ref "U50") (pin "J4") (pinfunction "VSS_J4") (pintype "power_in"))
      (node (ref "U50") (pin "J5") (pinfunction "VSS_J5") (pintype "power_in"))
      (node (ref "U50") (pin "J6") (pinfunction "VSS_J6") (pintype "power_in"))
      (node (ref "U50") (pin "K4") (pinfunction "VSS_K4") (pintype "power_in"))
      (node (ref "U50") (pin "K5") (pinfunction "VSS_K5") (pintype "power_in"))
      (node (ref "U50") (pin "K6") (pinfunction "VSS_K6") (pintype "power_in"))
      (node (ref "U50") (pin "L5") (pinfunction "VSS_L5") (pintype "power_in"))
      (node (ref "U50") (pin "L6") (pinfunction "VSSC_L6") (pintype "power_in"))
      (node (ref "Y6") (pin "2") (pinfunction "GND_2") (pintype "passive"))
    )
    (net (code "29") (name "Net-(C298-Pad1)") (class "Default")
      (node (ref "C298") (pin "1") (pinfunction "1_1") (pintype "passive"))
      (node (ref "R207") (pin "1") (pinfunction "1_1") (pintype "passive"))
      (node (ref "R208") (pin "1") (pinfunction "1_1") (pintype "passive"))
    )
    (net (code "30") (name "Net-(C299-Pad1)") (class "Default")
      (node (ref "C299") (pin "1") (pinfunction "1_1") (pintype "passive"))
      (node (ref "R209") (pin "1") (pinfunction "1_1") (pintype "passive"))
      (node (ref "R210") (pin "1") (pinfunction "1_1") (pintype "passive"))
    )
    (net (code "31") (name "Net-(C300-Pad1)") (class "Default")
      (node (ref "C300") (pin "1") (pinfunction "1_1") (pintype "passive"))
      (node (ref "R211") (pin "1") (pinfunction "1_1") (pintype "passive"))
      (node (ref "R212") (pin "1") (pinfunction "1_1") (pintype "passive"))
    )
    (net (code "32") (name "Net-(C301-Pad1)") (class "Default")
      (node (ref "C301") (pin "1") (pinfunction "1_1") (pintype "passive"))
      (node (ref "R213") (pin "1") (pinfunction "1_1") (pintype "passive"))
      (node (ref "R214") (pin "1") (pinfunction "1_1") (pintype "passive"))
    )
    (net (code "33") (name "Net-(DS3-K)") (class "Default")
      (node (ref "DS3") (pin "1") (pinfunction "K_1") (pintype "passive"))
      (node (ref "R237") (pin "2") (pinfunction "2_2") (pintype "passive"))
    )
    (net (code "34") (name "Net-(DS4-K)") (class "Default")
      (node (ref "DS4") (pin "1") (pinfunction "K_1") (pintype "passive"))
      (node (ref "R244") (pin "2") (pinfunction "2_2") (pintype "passive"))
    )
    (net (code "35") (name "Net-(DS5-K)") (class "Default")
      (node (ref "DS5") (pin "1") (pinfunction "K_1") (pintype "passive"))
      (node (ref "R247") (pin "2") (pinfunction "2_2") (pintype "passive"))
    )
    (net (code "36") (name "Net-(DS6-K)") (class "Default")
      (node (ref "DS6") (pin "1") (pinfunction "K_1") (pintype "passive"))
      (node (ref "R248") (pin "2") (pinfunction "2_2") (pintype "passive"))
    )
    (net (code "37") (name "Net-(U2G-GMC0_RXCLK)") (class "Default")
      (node (ref "R221") (pin "1") (pinfunction "1_1") (pintype "passive"))
      (node (ref "U2") (pin "AN28") (pinfunction "GMC0_RXCLK_AN28") (pintype "input"))
    )
    (net (code "38") (name "Net-(U2G-GMC0_RXCTL)") (class "Default")
      (node (ref "R220") (pin "1") (pinfunction "1_1") (pintype "passive"))
      (node (ref "U2") (pin "AJ31") (pinfunction "GMC0_RXCTL_AJ31") (pintype "input"))
    )
    (net (code "39") (name "Net-(U2G-GMC0_RXD0)") (class "Default")
      (node (ref "R215") (pin "1") (pinfunction "1_1") (pintype "passive"))
      (node (ref "U2") (pin "AL28") (pinfunction "GMC0_RXD0_AL28") (pintype "input"))
    )
    (net (code "40") (name "Net-(U2G-GMC0_RXD1)") (class "Default")
      (node (ref "R216") (pin "1") (pinfunction "1_1") (pintype "passive"))
      (node (ref "U2") (pin "AP29") (pinfunction "GMC0_RXD1_AP29") (pintype "input"))
    )
    (net (code "41") (name "Net-(U2G-GMC0_RXD2)") (class "Default")
      (node (ref "R217") (pin "1") (pinfunction "1_1") (pintype "passive"))
      (node (ref "U2") (pin "AM28") (pinfunction "GMC0_RXD2_AM28") (pintype "input"))
    )
    (net (code "42") (name "Net-(U2G-GMC0_RXD3)") (class "Default")
      (node (ref "R218") (pin "1") (pinfunction "1_1") (pintype "passive"))
      (node (ref "U2") (pin "AN29") (pinfunction "GMC0_RXD3_AN29") (pintype "input"))
    )
    (net (code "43") (name "Net-(U2G-GMC0_TXCLK)") (class "Default")
      (node (ref "R206") (pin "1") (pinfunction "1_1") (pintype "passive"))
      (node (ref "U2") (pin "AM27") (pinfunction "GMC0_TXCLK_AM27") (pintype "output"))
    )
    (net (code "44") (name "Net-(U2G-GMC0_TXCTL)") (class "Default")
      (node (ref "R205") (pin "1") (pinfunction "1_1") (pintype "passive"))
      (node (ref "U2") (pin "AN24") (pinfunction "GMC0_TXCTL_AN24") (pintype "output"))
    )
    (net (code "45") (name "Net-(U2G-GMC0_TXD0)") (class "Default")
      (node (ref "R201") (pin "1") (pinfunction "1_1") (pintype "passive"))
      (node (ref "U2") (pin "AL24") (pinfunction "GMC0_TXD0_AL24") (pintype "output"))
    )
    (net (code "46") (name "Net-(U2G-GMC0_TXD1)") (class "Default")
      (node (ref "R202") (pin "1") (pinfunction "1_1") (pintype "passive"))
      (node (ref "U2") (pin "AN25") (pinfunction "GMC0_TXD1_AN25") (pintype "output"))
    )
    (net (code "47") (name "Net-(U2G-GMC0_TXD2)") (class "Default")
      (node (ref "R203") (pin "1") (pinfunction "1_1") (pintype "passive"))
      (node (ref "U2") (pin "AM25") (pinfunction "GMC0_TXD2_AM25") (pintype "output"))
    )
    (net (code "48") (name "Net-(U2G-GMC0_TXD3)") (class "Default")
      (node (ref "R204") (pin "1") (pinfunction "1_1") (pintype "passive"))
      (node (ref "U2") (pin "AL25") (pinfunction "GMC0_TXD3_AL25") (pintype "output"))
    )
    (net (code "49") (name "Net-(U2G-GMCREFCLK)") (class "Default")
      (node (ref "R222") (pin "1") (pinfunction "1_1") (pintype "passive"))
      (node (ref "U2") (pin "AJ33") (pinfunction "GMCREFCLK_AJ33") (pintype "input"))
    )
    (net (code "50") (name "Net-(U2G-GMCTXCLK)") (class "Default")
      (node (ref "R238") (pin "2") (pinfunction "2_2") (pintype "passive"))
      (node (ref "U2") (pin "AL27") (pinfunction "GMCTXCLK_AL27") (pintype "input"))
    )
    (net (code "51") (name "Net-(U2I-GMC1_RXCLK)") (class "Default")
      (node (ref "R250") (pin "2") (pinfunction "2_2") (pintype "passive"))
      (node (ref "U2") (pin "AJ32") (pinfunction "GMC1_RXCLK_AJ32") (pintype "input"))
    )
    (net (code "52") (name "Net-(U2I-GMC1_RXCTL)") (class "Default")
      (node (ref "R251") (pin "2") (pinfunction "2_2") (pintype "passive"))
      (node (ref "U2") (pin "AL33") (pinfunction "GMC1_RXCTL_AL33") (pintype "input"))
    )
    (net (code "53") (name "Net-(U48-Y)") (class "Default")
      (node (ref "R219") (pin "1") (pinfunction "1_1") (pintype "passive"))
      (node (ref "U48") (pin "4") (pinfunction "Y_4") (pintype "output"))
    )
    (net (code "54") (name "Net-(U49-Y)") (class "Default")
      (node (ref "R227") (pin "1") (pinfunction "1_1") (pintype "passive"))
      (node (ref "U49") (pin "4") (pinfunction "Y_4") (pintype "output"))
    )
    (net (code "55") (name "Net-(U50A-125CLK)") (class "Default")
      (node (ref "R222") (pin "2") (pinfunction "2_2") (pintype "passive"))
      (node (ref "U50") (pin "K2") (pinfunction "125CLK_K2") (pintype "output"))
    )
    (net (code "56") (name "Net-(U50A-GTX_CLK)") (class "Default")
      (node (ref "R206") (pin "2") (pinfunction "2_2") (pintype "passive"))
      (node (ref "U50") (pin "E2") (pinfunction "GTX_CLK_E2") (pintype "input"))
    )
    (net (code "57") (name "Net-(U50A-RXD0)") (class "Default")
      (node (ref "R215") (pin "2") (pinfunction "2_2") (pintype "passive"))
      (node (ref "U50") (pin "B2") (pinfunction "RXD0_B2") (pintype "output"))
    )
    (net (code "58") (name "Net-(U50A-RXD1)") (class "Default")
      (node (ref "R216") (pin "2") (pinfunction "2_2") (pintype "passive"))
      (node (ref "U50") (pin "D3") (pinfunction "RXD1_D3") (pintype "output"))
    )
    (net (code "59") (name "Net-(U50A-RXD2)") (class "Default")
      (node (ref "R217") (pin "2") (pinfunction "2_2") (pintype "passive"))
      (node (ref "U50") (pin "C3") (pinfunction "RXD2_C3") (pintype "output"))
    )
    (net (code "60") (name "Net-(U50A-RXD3)") (class "Default")
      (node (ref "R218") (pin "2") (pinfunction "2_2") (pintype "passive"))
      (node (ref "U50") (pin "B3") (pinfunction "RXD3_B3") (pintype "output"))
    )
    (net (code "61") (name "Net-(U50A-RX_CLK)") (class "Default")
      (node (ref "R221") (pin "2") (pinfunction "2_2") (pintype "passive"))
      (node (ref "U50") (pin "C1") (pinfunction "RX_CLK_C1") (pintype "output"))
    )
    (net (code "62") (name "Net-(U50A-RX_DV)") (class "Default")
      (node (ref "R220") (pin "2") (pinfunction "2_2") (pintype "passive"))
      (node (ref "U50") (pin "B1") (pinfunction "RX_DV_B1") (pintype "output"))
    )
    (net (code "63") (name "Net-(U50A-TXD0)") (class "Default")
      (node (ref "R201") (pin "2") (pinfunction "2_2") (pintype "passive"))
      (node (ref "U50") (pin "F1") (pinfunction "TXD0_F1") (pintype "input"))
    )
    (net (code "64") (name "Net-(U50A-TXD1)") (class "Default")
      (node (ref "R202") (pin "2") (pinfunction "2_2") (pintype "passive"))
      (node (ref "U50") (pin "G2") (pinfunction "TXD1_G2") (pintype "input"))
    )
    (net (code "65") (name "Net-(U50A-TXD2)") (class "Default")
      (node (ref "R203") (pin "2") (pinfunction "2_2") (pintype "passive"))
      (node (ref "U50") (pin "G3") (pinfunction "TXD2_G3") (pintype "input"))
    )
    (net (code "66") (name "Net-(U50A-TXD3)") (class "Default")
      (node (ref "R204") (pin "2") (pinfunction "2_2") (pintype "passive"))
      (node (ref "U50") (pin "H2") (pinfunction "TXD3_H2") (pintype "input"))
    )
    (net (code "67") (name "Net-(U50A-TX_EN)") (class "Default")
      (node (ref "R205") (pin "2") (pinfunction "2_2") (pintype "passive"))
      (node (ref "U50") (pin "E1") (pinfunction "TX_EN_E1") (pintype "input"))
    )
    (net (code "68") (name "Net-(U50B-COMA)") (class "Default")
      (node (ref "R229") (pin "2") (pinfunction "2_2") (pintype "passive"))
      (node (ref "U50") (pin "L4") (pinfunction "COMA_L4") (pintype "input"))
    )
    (net (code "69") (name "Net-(U50B-CONFIG[0])") (class "Default")
      (node (ref "R242") (pin "2") (pinfunction "2_2") (pintype "passive"))
      (node (ref "U50") (pin "D8") (pinfunction "CONFIG[0]_D8") (pintype "input"))
    )
    (net (code "70") (name "Net-(U50B-CONFIG[1])") (class "Default")
      (node (ref "R241") (pin "2") (pinfunction "2_2") (pintype "passive"))
      (node (ref "U50") (pin "E9") (pinfunction "CONFIG[1]_E9") (pintype "input"))
    )
    (net (code "71") (name "Net-(U50B-CONFIG[2])") (class "Default")
      (node (ref "R239") (pin "2") (pinfunction "2_2") (pintype "passive"))
      (node (ref "U50") (pin "F8") (pinfunction "CONFIG[2]_F8") (pintype "input"))
    )
    (net (code "72") (name "Net-(U50B-CONFIG[3])") (class "Default")
      (node (ref "R236") (pin "2") (pinfunction "2_2") (pintype "passive"))
      (node (ref "U50") (pin "G7") (pinfunction "CONFIG[3]_G7") (pintype "input"))
    )
    (net (code "73") (name "Net-(U50B-CONFIG[4])") (class "Default")
      (node (ref "R234") (pin "2") (pinfunction "2_2") (pintype "passive"))
      (node (ref "U50") (pin "F9") (pinfunction "CONFIG[4]_F9") (pintype "input"))
    )
    (net (code "74") (name "Net-(U50B-CONFIG[5])") (class "Default")
      (node (ref "R233") (pin "2") (pinfunction "2_2") (pintype "passive"))
      (node (ref "U50") (pin "G9") (pinfunction "CONFIG[5]_G9") (pintype "input"))
    )
    (net (code "75") (name "Net-(U50B-CONFIG[6])") (class "Default")
      (node (ref "R232") (pin "2") (pinfunction "2_2") (pintype "passive"))
      (node (ref "U50") (pin "G8") (pinfunction "CONFIG[6]_G8") (pintype "input"))
    )
    (net (code "76") (name "Net-(U50B-HSDAC+)") (class "Default")
      (node (ref "TP10") (pin "1") (pinfunction "1_1") (pintype "passive"))
      (node (ref "U50") (pin "M5") (pinfunction "HSDAC+_M5") (pintype "passive"))
    )
    (net (code "77") (name "Net-(U50B-HSDAC-)") (class "Default")
      (node (ref "TP11") (pin "1") (pinfunction "1_1") (pintype "passive"))
      (node (ref "U50") (pin "M6") (pinfunction "HSDAC-_M6") (pintype "passive"))
    )
    (net (code "78") (name "Net-(U50B-RESETn)") (class "Default")
      (node (ref "R231") (pin "2") (pinfunction "2_2") (pintype "passive"))
      (node (ref "U50") (pin "K3") (pinfunction "RESETn_K3") (pintype "input"))
    )
    (net (code "79") (name "Net-(U50B-RSET)") (class "Default")
      (node (ref "R245") (pin "2") (pinfunction "2_2") (pintype "passive"))
      (node (ref "U50") (pin "M2") (pinfunction "RSET_M2") (pintype "input"))
    )
    (net (code "80") (name "Net-(U50B-SEL_FREQ)") (class "Default")
      (node (ref "R246") (pin "2") (pinfunction "2_2") (pintype "passive"))
      (node (ref "U50") (pin "H8") (pinfunction "SEL_FREQ_H8") (pintype "input"))
    )
    (net (code "81") (name "Net-(Y6-OUT)") (class "Default")
      (node (ref "R495") (pin "1") (pinfunction "1_1") (pintype "passive"))
      (node (ref "Y6") (pin "3") (pinfunction "OUT_3") (pintype "passive"))
    )
    (net (code "82") (name "PPCNET_AVDD") (class "Default")
      (node (ref "C274") (pin "2") (pinfunction "2_2") (pintype "passive"))
      (node (ref "C275") (pin "2") (pinfunction "2_2") (pintype "passive"))
      (node (ref "C276") (pin "2") (pinfunction "2_2") (pintype "passive"))
      (node (ref "C277") (pin "2") (pinfunction "2_2") (pintype "passive"))
      (node (ref "C278") (pin "2") (pinfunction "2_2") (pintype "passive"))
      (node (ref "C279") (pin "2") (pinfunction "2_2") (pintype "passive"))
      (node (ref "L21") (pin "2") (pinfunction "2_2") (pintype "passive"))
      (node (ref "U50") (pin "B7") (pinfunction "AVDD_B7") (pintype "power_in"))
      (node (ref "U50") (pin "M3") (pinfunction "AVDD_M3") (pintype "power_in"))
      (node (ref "U50") (pin "M4") (pinfunction "AVDD_M4") (pintype "power_in"))
      (node (ref "U50") (pin "M7") (pinfunction "AVDD_M7") (pintype "power_in"))
      (node (ref "U50") (pin "M8") (pinfunction "AVDD_M8") (pintype "power_in"))
      (node (ref "U50") (pin "N5") (pinfunction "AVDD_N5") (pintype "power_in"))
    )
    (net (code "83") (name "unconnected-(P9-MNT1-Pad15)") (class "Default")
      (node (ref "P9") (pin "15") (pinfunction "MNT1_15") (pintype "passive+no_connect"))
    )
    (net (code "84") (name "unconnected-(P9-MNT2-Pad16)") (class "Default")
      (node (ref "P9") (pin "16") (pinfunction "MNT2_16") (pintype "passive+no_connect"))
    )
    (net (code "85") (name "unconnected-(U2G-REJECTPKT0-PadAM23)") (class "Default")
      (node (ref "U2") (pin "AM23") (pinfunction "REJECTPKT0_AM23") (pintype "input+no_connect"))
    )
    (net (code "86") (name "unconnected-(U2G-REJECTPKT1-PadAL23)") (class "Default")
      (node (ref "U2") (pin "AL23") (pinfunction "REJECTPKT1_AL23") (pintype "input+no_connect"))
    )
    (net (code "87") (name "unconnected-(U2I-GMC1_RXD0-PadAM29)") (class "Default")
      (node (ref "U2") (pin "AM29") (pinfunction "GMC1_RXD0_AM29") (pintype "output+no_connect"))
    )
    (net (code "88") (name "unconnected-(U2I-GMC1_RXD1-PadAP30)") (class "Default")
      (node (ref "U2") (pin "AP30") (pinfunction "GMC1_RXD1_AP30") (pintype "input+no_connect"))
    )
    (net (code "89") (name "unconnected-(U2I-GMC1_RXD2-PadAP31)") (class "Default")
      (node (ref "U2") (pin "AP31") (pinfunction "GMC1_RXD2_AP31") (pintype "input+no_connect"))
    )
    (net (code "90") (name "unconnected-(U2I-GMC1_RXD3-PadAM30)") (class "Default")
      (node (ref "U2") (pin "AM30") (pinfunction "GMC1_RXD3_AM30") (pintype "input+no_connect"))
    )
    (net (code "91") (name "unconnected-(U2I-GMC1_TXCLK-PadAK32)") (class "Default")
      (node (ref "U2") (pin "AK32") (pinfunction "GMC1_TXCLK_AK32") (pintype "output+no_connect"))
    )
    (net (code "92") (name "unconnected-(U2I-GMC1_TXCTL-PadAM24)") (class "Default")
      (node (ref "U2") (pin "AM24") (pinfunction "GMC1_TXCTL_AM24") (pintype "output+no_connect"))
    )
    (net (code "93") (name "unconnected-(U2I-GMC1_TXD0-PadAP26)") (class "Default")
      (node (ref "U2") (pin "AP26") (pinfunction "GMC1_TXD0_AP26") (pintype "output+no_connect"))
    )
    (net (code "94") (name "unconnected-(U2I-GMC1_TXD1-PadAL26)") (class "Default")
      (node (ref "U2") (pin "AL26") (pinfunction "GMC1_TXD1_AL26") (pintype "output+no_connect"))
    )
    (net (code "95") (name "unconnected-(U2I-GMC1_TXD2-PadAN26)") (class "Default")
      (node (ref "U2") (pin "AN26") (pinfunction "GMC1_TXD2_AN26") (pintype "output+no_connect"))
    )
    (net (code "96") (name "unconnected-(U2I-GMC1_TXD3-PadAM26)") (class "Default")
      (node (ref "U2") (pin "AM26") (pinfunction "GMC1_TXD3_AM26") (pintype "output+no_connect"))
    )
    (net (code "97") (name "unconnected-(U50A-COL-PadB6)") (class "Default")
      (node (ref "U50") (pin "B6") (pinfunction "COL_B6") (pintype "output+no_connect"))
    )
    (net (code "98") (name "unconnected-(U50A-CRS-PadB5)") (class "Default")
      (node (ref "U50") (pin "B5") (pinfunction "CRS_B5") (pintype "output+no_connect"))
    )
    (net (code "99") (name "unconnected-(U50A-RXD4-PadC4)") (class "Default")
      (node (ref "U50") (pin "C4") (pinfunction "RXD4_C4") (pintype "output+no_connect"))
    )
    (net (code "100") (name "unconnected-(U50A-RXD5-PadA1)") (class "Default")
      (node (ref "U50") (pin "A1") (pinfunction "RXD5_A1") (pintype "output+no_connect"))
    )
    (net (code "101") (name "unconnected-(U50A-RXD6-PadA2)") (class "Default")
      (node (ref "U50") (pin "A2") (pinfunction "RXD6_A2") (pintype "output+no_connect"))
    )
    (net (code "102") (name "unconnected-(U50A-RXD7-PadC5)") (class "Default")
      (node (ref "U50") (pin "C5") (pinfunction "RXD7_C5") (pintype "output+no_connect"))
    )
    (net (code "103") (name "unconnected-(U50A-RX_ER-PadD2)") (class "Default")
      (node (ref "U50") (pin "D2") (pinfunction "RX_ER_D2") (pintype "output+no_connect"))
    )
    (net (code "104") (name "unconnected-(U50A-S_CLK+-PadA5)") (class "Default")
      (node (ref "U50") (pin "A5") (pinfunction "S_CLK+_A5") (pintype "input+no_connect"))
    )
    (net (code "105") (name "unconnected-(U50A-S_CLK--PadA6)") (class "Default")
      (node (ref "U50") (pin "A6") (pinfunction "S_CLK-_A6") (pintype "input+no_connect"))
    )
    (net (code "106") (name "unconnected-(U50A-S_IN+-PadA3)") (class "Default")
      (node (ref "U50") (pin "A3") (pinfunction "S_IN+_A3") (pintype "input+no_connect"))
    )
    (net (code "107") (name "unconnected-(U50A-S_IN--PadA4)") (class "Default")
      (node (ref "U50") (pin "A4") (pinfunction "S_IN-_A4") (pintype "input+no_connect"))
    )
    (net (code "108") (name "unconnected-(U50A-S_OUT+-PadA7)") (class "Default")
      (node (ref "U50") (pin "A7") (pinfunction "S_OUT+_A7") (pintype "output+no_connect"))
    )
    (net (code "109") (name "unconnected-(U50A-S_OUT--PadA8)") (class "Default")
      (node (ref "U50") (pin "A8") (pinfunction "S_OUT-_A8") (pintype "output+no_connect"))
    )
    (net (code "110") (name "unconnected-(U50A-TXD4-PadH1)") (class "Default")
      (node (ref "U50") (pin "H1") (pinfunction "TXD4_H1") (pintype "input+no_connect"))
    )
    (net (code "111") (name "unconnected-(U50A-TXD5-PadH3)") (class "Default")
      (node (ref "U50") (pin "H3") (pinfunction "TXD5_H3") (pintype "input+no_connect"))
    )
    (net (code "112") (name "unconnected-(U50A-TXD6-PadJ1)") (class "Default")
      (node (ref "U50") (pin "J1") (pinfunction "TXD6_J1") (pintype "input+no_connect"))
    )
    (net (code "113") (name "unconnected-(U50A-TXD7-PadJ2)") (class "Default")
      (node (ref "U50") (pin "J2") (pinfunction "TXD7_J2") (pintype "input+no_connect"))
    )
    (net (code "114") (name "unconnected-(U50A-TX_CLK-PadD1)") (class "Default")
      (node (ref "U50") (pin "D1") (pinfunction "TX_CLK_D1") (pintype "output+no_connect"))
    )
    (net (code "115") (name "unconnected-(U50A-TX_ER-PadF2)") (class "Default")
      (node (ref "U50") (pin "F2") (pinfunction "TX_ER_F2") (pintype "input+no_connect"))
    )
    (net (code "116") (name "unconnected-(U50B-NC-PadG1)") (class "Default")
      (node (ref "U50") (pin "G1") (pinfunction "NC_G1") (pintype "passive+no_connect"))
    )
    (net (code "117") (name "unconnected-(U50B-NC-PadK7)") (class "Default")
      (node (ref "U50") (pin "K7") (pinfunction "NC_K7") (pintype "passive+no_connect"))
    )
    (net (code "118") (name "unconnected-(U50B-XTAL2-PadJ9)") (class "Default")
      (node (ref "U50") (pin "J9") (pinfunction "XTAL2_J9") (pintype "input+no_connect"))
    )
    (net (code "119") (name "unconnected-(U50C-TRSTn-PadM9)") (class "Default")
      (node (ref "U50") (pin "M9") (pinfunction "TRSTn_M9") (pintype "input+no_connect"))
    )
    (net (code "120") (name "unconnected-(Y6-EN-Pad1)") (class "Default")
      (node (ref "Y6") (pin "1") (pinfunction "EN_1") (pintype "passive+no_connect"))
    )
  )
)
